# bldc-robot-main-board.net
KiCad netlist of a schematic drawn in Altium Designer
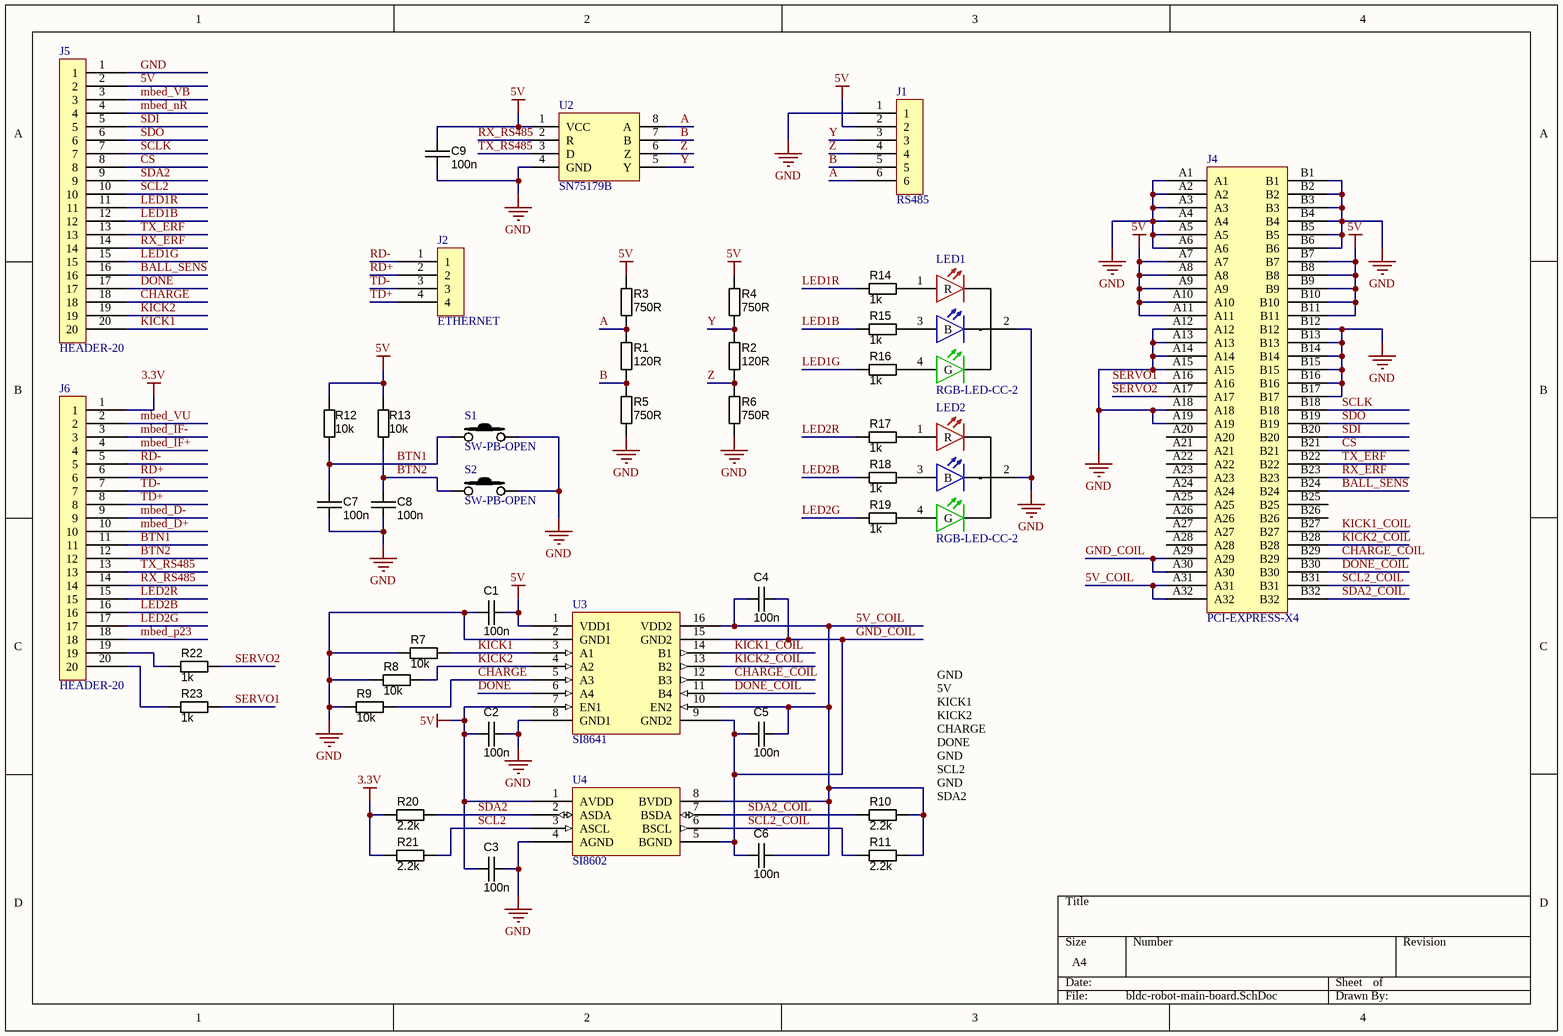
[diagram p0: bldc-robot-main-board.SchDoc]

(export (version "E")
  (design (tool "Eeschema 10.0.6"))
  (components
    (comp (ref "C1")
      (value "100n")
      (footprint "CAPC1608X90N")
      (description "Capacitor SMD Cer 100nF 10% 50V X7R 0603")
      (fields (field (name "TOLERANCE") "±10%"))
      (libsource (lib "PBL - Capacitors") (part "CAPC_100n_0603_X7R_50V_10%"))
    )
    (comp (ref "C2")
      (value "100n")
      (footprint "CAPC1608X90N")
      (description "Capacitor SMD Cer 100nF 10% 50V X7R 0603")
      (fields (field (name "TOLERANCE") "±10%"))
      (libsource (lib "PBL - Capacitors") (part "CAPC_100n_0603_X7R_50V_10%"))
    )
    (comp (ref "C3")
      (value "100n")
      (footprint "CAPC1608X90N")
      (description "Capacitor SMD Cer 100nF 10% 50V X7R 0603")
      (fields (field (name "TOLERANCE") "±10%"))
      (libsource (lib "PBL - Capacitors") (part "CAPC_100n_0603_X7R_50V_10%"))
    )
    (comp (ref "C4")
      (value "100n")
      (footprint "CAPC1608X90N")
      (description "Capacitor SMD Cer 100nF 10% 50V X7R 0603")
      (fields (field (name "TOLERANCE") "±10%"))
      (libsource (lib "PBL - Capacitors") (part "CAPC_100n_0603_X7R_50V_10%"))
    )
    (comp (ref "C5")
      (value "100n")
      (footprint "CAPC1608X90N")
      (description "Capacitor SMD Cer 100nF 10% 50V X7R 0603")
      (fields (field (name "TOLERANCE") "±10%"))
      (libsource (lib "PBL - Capacitors") (part "CAPC_100n_0603_X7R_50V_10%"))
    )
    (comp (ref "C6")
      (value "100n")
      (footprint "CAPC1608X90N")
      (description "Capacitor SMD Cer 100nF 10% 50V X7R 0603")
      (fields (field (name "TOLERANCE") "±10%"))
      (libsource (lib "PBL - Capacitors") (part "CAPC_100n_0603_X7R_50V_10%"))
    )
    (comp (ref "C7")
      (value "100n")
      (footprint "CAPC1608X90N")
      (description "Capacitor SMD Cer 100nF 10% 50V X7R 0603")
      (fields (field (name "TOLERANCE") "±10%"))
      (libsource (lib "PBL - Capacitors") (part "CAPC_100n_0603_X7R_50V_10%"))
    )
    (comp (ref "C8")
      (value "100n")
      (footprint "CAPC1608X90N")
      (description "Capacitor SMD Cer 100nF 10% 50V X7R 0603")
      (fields (field (name "TOLERANCE") "±10%"))
      (libsource (lib "PBL - Capacitors") (part "CAPC_100n_0603_X7R_50V_10%"))
    )
    (comp (ref "C9")
      (value "100n")
      (footprint "CAPC1608X90N")
      (description "Capacitor SMD Cer 100nF 10% 50V X7R 0603")
      (fields (field (name "TOLERANCE") "±10%"))
      (libsource (lib "PBL - Capacitors") (part "CAPC_100n_0603_X7R_50V_10%"))
    )
    (comp (ref "J1")
      (value "RS485")
      (footprint "MICRO-MATCH-6")
      (libsource (lib "connectors") (part "HEADER-6"))
    )
    (comp (ref "J2")
      (value "ETHERNET")
      (footprint "MICRO-MATCH-4")
      (libsource (lib "connectors") (part "HEADER-4"))
    )
    (comp (ref "J4")
      (value "PCI-EXPRESS-X4")
      (footprint "PCI-EXPRESS-X4-CARD-EDGE")
      (libsource (lib "connectors") (part "PCI-EXPRESS-X4"))
    )
    (comp (ref "J5")
      (value "HEADER-20")
      (footprint "MICRO-MATCH-20")
      (libsource (lib "connectors") (part "HEADER-20"))
    )
    (comp (ref "J6")
      (value "HEADER-20")
      (footprint "MICRO-MATCH-20")
      (libsource (lib "connectors") (part "HEADER-20"))
    )
    (comp (ref "LED1")
      (value "RGB-LED-CC-2")
      (footprint "RGB-LED-5mm")
      (libsource (lib "misc") (part "RGB-LED-CC-2"))
    )
    (comp (ref "LED2")
      (value "RGB-LED-CC-2")
      (footprint "RGB-LED-5mm")
      (libsource (lib "misc") (part "RGB-LED-CC-2"))
    )
    (comp (ref "R1")
      (value "120R")
      (footprint "RESC1608X55N")
      (description "Resistor SMD chip 120 Ohm 0.1W 5% 0603")
      (fields (field (name "TOLERANCE") "±5%"))
      (libsource (lib "") (part "RES_120R_0603_5%_2"))
    )
    (comp (ref "R2")
      (value "120R")
      (footprint "RESC1608X55N")
      (description "Resistor SMD chip 120 Ohm 0.1W 5% 0603")
      (fields (field (name "TOLERANCE") "±5%"))
      (libsource (lib "") (part "RES_120R_0603_5%_2"))
    )
    (comp (ref "R3")
      (value "750R")
      (footprint "RESC1608X55N")
      (description "Resistor SMD chip 120 Ohm 0.1W 5% 0603")
      (fields (field (name "TOLERANCE") "±5%"))
      (libsource (lib "") (part "RES_120R_0603_5%_2"))
    )
    (comp (ref "R4")
      (value "750R")
      (footprint "RESC1608X55N")
      (description "Resistor SMD chip 120 Ohm 0.1W 5% 0603")
      (fields (field (name "TOLERANCE") "±5%"))
      (libsource (lib "") (part "RES_120R_0603_5%_2"))
    )
    (comp (ref "R5")
      (value "750R")
      (footprint "RESC1608X55N")
      (description "Resistor SMD chip 120 Ohm 0.1W 5% 0603")
      (fields (field (name "TOLERANCE") "±5%"))
      (libsource (lib "") (part "RES_120R_0603_5%_2"))
    )
    (comp (ref "R6")
      (value "750R")
      (footprint "RESC1608X55N")
      (description "Resistor SMD chip 120 Ohm 0.1W 5% 0603")
      (fields (field (name "TOLERANCE") "±5%"))
      (libsource (lib "") (part "RES_120R_0603_5%_2"))
    )
    (comp (ref "R7")
      (value "10k")
      (footprint "RESC1608X55N")
      (description "Resistor SMD chip 120 Ohm 0.1W 5% 0603")
      (fields (field (name "TOLERANCE") "±5%"))
      (libsource (lib "") (part "RES_120R_0603_5%_1"))
    )
    (comp (ref "R8")
      (value "10k")
      (footprint "RESC1608X55N")
      (description "Resistor SMD chip 120 Ohm 0.1W 5% 0603")
      (fields (field (name "TOLERANCE") "±5%"))
      (libsource (lib "") (part "RES_120R_0603_5%_1"))
    )
    (comp (ref "R9")
      (value "10k")
      (footprint "RESC1608X55N")
      (description "Resistor SMD chip 120 Ohm 0.1W 5% 0603")
      (fields (field (name "TOLERANCE") "±5%"))
      (libsource (lib "") (part "RES_120R_0603_5%_1"))
    )
    (comp (ref "R10")
      (value "2.2k")
      (footprint "RESC1608X55N")
      (description "Resistor SMD chip 120 Ohm 0.1W 5% 0603")
      (fields (field (name "TOLERANCE") "±5%"))
      (libsource (lib "") (part "RES_120R_0603_5%_1"))
    )
    (comp (ref "R11")
      (value "2.2k")
      (footprint "RESC1608X55N")
      (description "Resistor SMD chip 120 Ohm 0.1W 5% 0603")
      (fields (field (name "TOLERANCE") "±5%"))
      (libsource (lib "") (part "RES_120R_0603_5%_1"))
    )
    (comp (ref "R12")
      (value "10k")
      (footprint "RESC1608X55N")
      (description "Resistor SMD chip 120 Ohm 0.1W 5% 0603")
      (fields (field (name "TOLERANCE") "±5%"))
      (libsource (lib "PBL - Resistors") (part "RES_120R_0603_5%"))
    )
    (comp (ref "R13")
      (value "10k")
      (footprint "RESC1608X55N")
      (description "Resistor SMD chip 120 Ohm 0.1W 5% 0603")
      (fields (field (name "TOLERANCE") "±5%"))
      (libsource (lib "PBL - Resistors") (part "RES_120R_0603_5%"))
    )
    (comp (ref "R14")
      (value "1k")
      (footprint "RESC1608X55N")
      (description "Resistor SMD chip 120 Ohm 0.1W 5% 0603")
      (fields (field (name "TOLERANCE") "±5%"))
      (libsource (lib "") (part "RES_120R_0603_5%_1"))
    )
    (comp (ref "R15")
      (value "1k")
      (footprint "RESC1608X55N")
      (description "Resistor SMD chip 120 Ohm 0.1W 5% 0603")
      (fields (field (name "TOLERANCE") "±5%"))
      (libsource (lib "") (part "RES_120R_0603_5%_1"))
    )
    (comp (ref "R16")
      (value "1k")
      (footprint "RESC1608X55N")
      (description "Resistor SMD chip 120 Ohm 0.1W 5% 0603")
      (fields (field (name "TOLERANCE") "±5%"))
      (libsource (lib "") (part "RES_120R_0603_5%_1"))
    )
    (comp (ref "R17")
      (value "1k")
      (footprint "RESC1608X55N")
      (description "Resistor SMD chip 120 Ohm 0.1W 5% 0603")
      (fields (field (name "TOLERANCE") "±5%"))
      (libsource (lib "") (part "RES_120R_0603_5%_1"))
    )
    (comp (ref "R18")
      (value "1k")
      (footprint "RESC1608X55N")
      (description "Resistor SMD chip 120 Ohm 0.1W 5% 0603")
      (fields (field (name "TOLERANCE") "±5%"))
      (libsource (lib "") (part "RES_120R_0603_5%_1"))
    )
    (comp (ref "R19")
      (value "1k")
      (footprint "RESC1608X55N")
      (description "Resistor SMD chip 120 Ohm 0.1W 5% 0603")
      (fields (field (name "TOLERANCE") "±5%"))
      (libsource (lib "") (part "RES_120R_0603_5%_1"))
    )
    (comp (ref "R20")
      (value "2.2k")
      (footprint "RESC1608X55N")
      (description "Resistor SMD chip 120 Ohm 0.1W 5% 0603")
      (fields (field (name "TOLERANCE") "±5%"))
      (libsource (lib "") (part "RES_120R_0603_5%_1"))
    )
    (comp (ref "R21")
      (value "2.2k")
      (footprint "RESC1608X55N")
      (description "Resistor SMD chip 120 Ohm 0.1W 5% 0603")
      (fields (field (name "TOLERANCE") "±5%"))
      (libsource (lib "") (part "RES_120R_0603_5%_1"))
    )
    (comp (ref "R22")
      (value "1k")
      (footprint "RESC1608X55N")
      (description "Resistor SMD chip 120 Ohm 0.1W 5% 0603")
      (fields (field (name "TOLERANCE") "±5%"))
      (libsource (lib "") (part "RES_120R_0603_5%_1"))
    )
    (comp (ref "R23")
      (value "1k")
      (footprint "RESC1608X55N")
      (description "Resistor SMD chip 120 Ohm 0.1W 5% 0603")
      (fields (field (name "TOLERANCE") "±5%"))
      (libsource (lib "") (part "RES_120R_0603_5%_1"))
    )
    (comp (ref "S1")
      (value "SW-PB-OPEN")
      (footprint "MC8US9R2A2M7RES")
      (libsource (lib "switches") (part "SW-PB-OPEN"))
    )
    (comp (ref "S2")
      (value "SW-PB-OPEN")
      (footprint "MC8US9R2A2M7RES")
      (libsource (lib "switches") (part "SW-PB-OPEN"))
    )
    (comp (ref "U2")
      (value "SN75179B")
      (footprint "SOIC-8")
      (libsource (lib "texas_instruments") (part "SN75179B"))
    )
    (comp (ref "U3") (value "SI8641") (footprint "SOIC16") (libsource (lib "digital") (part "SI8641")))
    (comp (ref "U4") (value "SI8602") (footprint "SOIC8") (libsource (lib "digital") (part "SI8602")))
  )
  (nets
    (net (code "1") (name "/5V_COIL") (class "Default")
      (node (ref "C4") (pin "2") (pintype "passive"))
      (node (ref "C5") (pin "1") (pintype "passive"))
      (node (ref "C6") (pin "1") (pintype "passive"))
      (node (ref "J4") (pin "A31") (pinfunction "A31_A31") (pintype "passive"))
      (node (ref "J4") (pin "A32") (pinfunction "A32_A32") (pintype "passive"))
      (node (ref "R10") (pin "2") (pinfunction "2_2") (pintype "passive"))
      (node (ref "R11") (pin "2") (pinfunction "2_2") (pintype "passive"))
      (node (ref "U3") (pin "10") (pinfunction "EN2_10") (pintype "input"))
      (node (ref "U3") (pin "16") (pinfunction "VDD2_16") (pintype "power_in"))
      (node (ref "U4") (pin "8") (pinfunction "BVDD_8") (pintype "power_in"))
    )
    (net (code "2") (name "/A") (class "Default")
      (node (ref "J1") (pin "6") (pinfunction "6_6") (pintype "passive"))
      (node (ref "R1") (pin "1") (pinfunction "1_1") (pintype "passive"))
      (node (ref "R3") (pin "2") (pinfunction "2_2") (pintype "passive"))
      (node (ref "U2") (pin "8") (pinfunction "A_8") (pintype "passive"))
    )
    (net (code "3") (name "/B") (class "Default")
      (node (ref "J1") (pin "5") (pinfunction "5_5") (pintype "passive"))
      (node (ref "R1") (pin "2") (pinfunction "2_2") (pintype "passive"))
      (node (ref "R5") (pin "1") (pinfunction "1_1") (pintype "passive"))
      (node (ref "U2") (pin "7") (pinfunction "B_7") (pintype "passive"))
    )
    (net (code "4") (name "/BALL_SENS") (class "Default")
      (node (ref "J4") (pin "B24") (pinfunction "B24_B24") (pintype "passive"))
      (node (ref "J5") (pin "16") (pinfunction "16_16") (pintype "passive"))
    )
    (net (code "5") (name "/BTN1") (class "Default")
      (node (ref "C7") (pin "1") (pintype "passive"))
      (node (ref "J6") (pin "11") (pinfunction "11_11") (pintype "passive"))
      (node (ref "R12") (pin "1") (pinfunction "1_1") (pintype "passive"))
      (node (ref "S1") (pin "1") (pinfunction "1_1") (pintype "passive"))
    )
    (net (code "6") (name "/BTN2") (class "Default")
      (node (ref "C8") (pin "1") (pintype "passive"))
      (node (ref "J6") (pin "12") (pinfunction "12_12") (pintype "passive"))
      (node (ref "R13") (pin "1") (pinfunction "1_1") (pintype "passive"))
      (node (ref "S2") (pin "1") (pinfunction "1_1") (pintype "passive"))
    )
    (net (code "7") (name "/CHARGE") (class "Default")
      (node (ref "J5") (pin "18") (pinfunction "18_18") (pintype "passive"))
      (node (ref "R9") (pin "2") (pinfunction "2_2") (pintype "passive"))
      (node (ref "U3") (pin "5") (pinfunction "A3_5") (pintype "input"))
    )
    (net (code "8") (name "/CHARGE_COIL") (class "Default")
      (node (ref "J4") (pin "B29") (pinfunction "B29_B29") (pintype "passive"))
      (node (ref "U3") (pin "12") (pinfunction "B3_12") (pintype "output"))
    )
    (net (code "9") (name "/CS") (class "Default")
      (node (ref "J4") (pin "B21") (pinfunction "B21_B21") (pintype "passive"))
      (node (ref "J5") (pin "8") (pinfunction "8_8") (pintype "passive"))
    )
    (net (code "10") (name "/DONE") (class "Default")
      (node (ref "J5") (pin "17") (pinfunction "17_17") (pintype "passive"))
      (node (ref "U3") (pin "6") (pinfunction "A4_6") (pintype "input"))
    )
    (net (code "11") (name "/DONE_COIL") (class "Default")
      (node (ref "J4") (pin "B30") (pinfunction "B30_B30") (pintype "passive"))
      (node (ref "U3") (pin "11") (pinfunction "B4_11") (pintype "input"))
    )
    (net (code "12") (name "/GND_COIL") (class "Default")
      (node (ref "C4") (pin "1") (pintype "passive"))
      (node (ref "C5") (pin "2") (pintype "passive"))
      (node (ref "C6") (pin "2") (pintype "passive"))
      (node (ref "J4") (pin "A29") (pinfunction "A29_A29") (pintype "passive"))
      (node (ref "J4") (pin "A30") (pinfunction "A30_A30") (pintype "passive"))
      (node (ref "U3") (pin "15") (pinfunction "GND2_15") (pintype "power_in"))
      (node (ref "U3") (pin "9") (pinfunction "GND2_9") (pintype "power_in"))
      (node (ref "U4") (pin "5") (pinfunction "BGND_5") (pintype "power_in"))
    )
    (net (code "13") (name "/KICK1") (class "Default")
      (node (ref "J5") (pin "20") (pinfunction "20_20") (pintype "passive"))
      (node (ref "R7") (pin "2") (pinfunction "2_2") (pintype "passive"))
      (node (ref "U3") (pin "3") (pinfunction "A1_3") (pintype "input"))
    )
    (net (code "14") (name "/KICK1_COIL") (class "Default")
      (node (ref "J4") (pin "B27") (pinfunction "B27_B27") (pintype "passive"))
      (node (ref "U3") (pin "14") (pinfunction "B1_14") (pintype "output"))
    )
    (net (code "15") (name "/KICK2") (class "Default")
      (node (ref "J5") (pin "19") (pinfunction "19_19") (pintype "passive"))
      (node (ref "R8") (pin "2") (pinfunction "2_2") (pintype "passive"))
      (node (ref "U3") (pin "4") (pinfunction "A2_4") (pintype "input"))
    )
    (net (code "16") (name "/KICK2_COIL") (class "Default")
      (node (ref "J4") (pin "B28") (pinfunction "B28_B28") (pintype "passive"))
      (node (ref "U3") (pin "13") (pinfunction "B2_13") (pintype "output"))
    )
    (net (code "17") (name "/LED1B") (class "Default")
      (node (ref "J5") (pin "12") (pinfunction "12_12") (pintype "passive"))
      (node (ref "R15") (pin "1") (pinfunction "1_1") (pintype "passive"))
    )
    (net (code "18") (name "/LED1G") (class "Default")
      (node (ref "J5") (pin "15") (pinfunction "15_15") (pintype "passive"))
      (node (ref "R16") (pin "1") (pinfunction "1_1") (pintype "passive"))
    )
    (net (code "19") (name "/LED1R") (class "Default")
      (node (ref "J5") (pin "11") (pinfunction "11_11") (pintype "passive"))
      (node (ref "R14") (pin "1") (pinfunction "1_1") (pintype "passive"))
    )
    (net (code "20") (name "/LED2B") (class "Default")
      (node (ref "J6") (pin "16") (pinfunction "16_16") (pintype "passive"))
      (node (ref "R18") (pin "1") (pinfunction "1_1") (pintype "passive"))
    )
    (net (code "21") (name "/LED2G") (class "Default")
      (node (ref "J6") (pin "17") (pinfunction "17_17") (pintype "passive"))
      (node (ref "R19") (pin "1") (pinfunction "1_1") (pintype "passive"))
    )
    (net (code "22") (name "/LED2R") (class "Default")
      (node (ref "J6") (pin "15") (pinfunction "15_15") (pintype "passive"))
      (node (ref "R17") (pin "1") (pinfunction "1_1") (pintype "passive"))
    )
    (net (code "23") (name "/RD+") (class "Default")
      (node (ref "J2") (pin "2") (pinfunction "2_2") (pintype "passive"))
      (node (ref "J6") (pin "6") (pinfunction "6_6") (pintype "passive"))
    )
    (net (code "24") (name "/RD-") (class "Default")
      (node (ref "J2") (pin "1") (pinfunction "1_1") (pintype "passive"))
      (node (ref "J6") (pin "5") (pinfunction "5_5") (pintype "passive"))
    )
    (net (code "25") (name "/RX_ERF") (class "Default")
      (node (ref "J4") (pin "B23") (pinfunction "B23_B23") (pintype "passive"))
      (node (ref "J5") (pin "14") (pinfunction "14_14") (pintype "passive"))
    )
    (net (code "26") (name "/RX_RS485") (class "Default")
      (node (ref "J6") (pin "14") (pinfunction "14_14") (pintype "passive"))
      (node (ref "U2") (pin "2") (pinfunction "R_2") (pintype "passive"))
    )
    (net (code "27") (name "/SCL2") (class "Default")
      (node (ref "J5") (pin "10") (pinfunction "10_10") (pintype "passive"))
      (node (ref "R21") (pin "2") (pinfunction "2_2") (pintype "passive"))
      (node (ref "U4") (pin "3") (pinfunction "ASCL_3") (pintype "input"))
    )
    (net (code "28") (name "/SCL2_COIL") (class "Default")
      (node (ref "J4") (pin "B31") (pinfunction "B31_B31") (pintype "passive"))
      (node (ref "R11") (pin "1") (pinfunction "1_1") (pintype "passive"))
      (node (ref "U4") (pin "6") (pinfunction "BSCL_6") (pintype "output"))
    )
    (net (code "29") (name "/SCLK") (class "Default")
      (node (ref "J4") (pin "B18") (pinfunction "B18_B18") (pintype "passive"))
      (node (ref "J5") (pin "7") (pinfunction "7_7") (pintype "passive"))
    )
    (net (code "30") (name "/SDA2") (class "Default")
      (node (ref "J5") (pin "9") (pinfunction "9_9") (pintype "passive"))
      (node (ref "R20") (pin "2") (pinfunction "2_2") (pintype "passive"))
      (node (ref "U4") (pin "2") (pinfunction "ASDA_2") (pintype "bidirectional"))
    )
    (net (code "31") (name "/SDA2_COIL") (class "Default")
      (node (ref "J4") (pin "B32") (pinfunction "B32_B32") (pintype "passive"))
      (node (ref "R10") (pin "1") (pinfunction "1_1") (pintype "passive"))
      (node (ref "U4") (pin "7") (pinfunction "BSDA_7") (pintype "bidirectional"))
    )
    (net (code "32") (name "/SDI") (class "Default")
      (node (ref "J4") (pin "B20") (pinfunction "B20_B20") (pintype "passive"))
      (node (ref "J5") (pin "5") (pinfunction "5_5") (pintype "passive"))
    )
    (net (code "33") (name "/SDO") (class "Default")
      (node (ref "J4") (pin "B19") (pinfunction "B19_B19") (pintype "passive"))
      (node (ref "J5") (pin "6") (pinfunction "6_6") (pintype "passive"))
    )
    (net (code "34") (name "/SERVO1") (class "Default")
      (node (ref "J4") (pin "A16") (pinfunction "A16_A16") (pintype "passive"))
      (node (ref "R23") (pin "2") (pinfunction "2_2") (pintype "passive"))
    )
    (net (code "35") (name "/SERVO2") (class "Default")
      (node (ref "J4") (pin "A17") (pinfunction "A17_A17") (pintype "passive"))
      (node (ref "R22") (pin "2") (pinfunction "2_2") (pintype "passive"))
    )
    (net (code "36") (name "/TD+") (class "Default")
      (node (ref "J2") (pin "4") (pinfunction "4_4") (pintype "passive"))
      (node (ref "J6") (pin "8") (pinfunction "8_8") (pintype "passive"))
    )
    (net (code "37") (name "/TD-") (class "Default")
      (node (ref "J2") (pin "3") (pinfunction "3_3") (pintype "passive"))
      (node (ref "J6") (pin "7") (pinfunction "7_7") (pintype "passive"))
    )
    (net (code "38") (name "/TX_ERF") (class "Default")
      (node (ref "J4") (pin "B22") (pinfunction "B22_B22") (pintype "passive"))
      (node (ref "J5") (pin "13") (pinfunction "13_13") (pintype "passive"))
    )
    (net (code "39") (name "/TX_RS485") (class "Default")
      (node (ref "J6") (pin "13") (pinfunction "13_13") (pintype "passive"))
      (node (ref "U2") (pin "3") (pinfunction "D_3") (pintype "passive"))
    )
    (net (code "40") (name "/Y") (class "Default")
      (node (ref "J1") (pin "3") (pinfunction "3_3") (pintype "passive"))
      (node (ref "R2") (pin "1") (pinfunction "1_1") (pintype "passive"))
      (node (ref "R4") (pin "2") (pinfunction "2_2") (pintype "passive"))
      (node (ref "U2") (pin "5") (pinfunction "Y_5") (pintype "passive"))
    )
    (net (code "41") (name "/Z") (class "Default")
      (node (ref "J1") (pin "4") (pinfunction "4_4") (pintype "passive"))
      (node (ref "R2") (pin "2") (pinfunction "2_2") (pintype "passive"))
      (node (ref "R6") (pin "1") (pinfunction "1_1") (pintype "passive"))
      (node (ref "U2") (pin "6") (pinfunction "Z_6") (pintype "passive"))
    )
    (net (code "42") (name "/mbed_D+") (class "Default")
      (node (ref "J6") (pin "10") (pinfunction "10_10") (pintype "passive"))
    )
    (net (code "43") (name "/mbed_D-") (class "Default")
      (node (ref "J6") (pin "9") (pinfunction "9_9") (pintype "passive"))
    )
    (net (code "44") (name "/mbed_IF+") (class "Default")
      (node (ref "J6") (pin "4") (pinfunction "4_4") (pintype "passive"))
    )
    (net (code "45") (name "/mbed_IF-") (class "Default")
      (node (ref "J6") (pin "3") (pinfunction "3_3") (pintype "passive"))
    )
    (net (code "46") (name "/mbed_VB") (class "Default")
      (node (ref "J5") (pin "3") (pinfunction "3_3") (pintype "passive"))
    )
    (net (code "47") (name "/mbed_VU") (class "Default")
      (node (ref "J6") (pin "2") (pinfunction "2_2") (pintype "passive"))
    )
    (net (code "48") (name "/mbed_nR") (class "Default")
      (node (ref "J5") (pin "4") (pinfunction "4_4") (pintype "passive"))
    )
    (net (code "49") (name "/mbed_p23") (class "Default")
      (node (ref "J6") (pin "18") (pinfunction "18_18") (pintype "passive"))
    )
    (net (code "50") (name "3.3V") (class "Default")
      (node (ref "J6") (pin "1") (pinfunction "1_1") (pintype "passive"))
      (node (ref "R20") (pin "1") (pinfunction "1_1") (pintype "passive"))
      (node (ref "R21") (pin "1") (pinfunction "1_1") (pintype "passive"))
    )
    (net (code "51") (name "5V") (class "Default")
      (node (ref "C1") (pin "1") (pintype "passive"))
      (node (ref "C2") (pin "2") (pintype "passive"))
      (node (ref "C3") (pin "2") (pintype "passive"))
      (node (ref "C9") (pin "1") (pintype "passive"))
      (node (ref "J1") (pin "2") (pinfunction "2_2") (pintype "passive"))
      (node (ref "J4") (pin "A10") (pinfunction "A10_A10") (pintype "passive"))
      (node (ref "J4") (pin "A11") (pinfunction "A11_A11") (pintype "passive"))
      (node (ref "J4") (pin "A7") (pinfunction "A7_A7") (pintype "passive"))
      (node (ref "J4") (pin "A8") (pinfunction "A8_A8") (pintype "passive"))
      (node (ref "J4") (pin "A9") (pinfunction "A9_A9") (pintype "passive"))
      (node (ref "J4") (pin "B10") (pinfunction "B10_B10") (pintype "passive"))
      (node (ref "J4") (pin "B11") (pinfunction "B11_B11") (pintype "passive"))
      (node (ref "J4") (pin "B7") (pinfunction "B7_B7") (pintype "passive"))
      (node (ref "J4") (pin "B8") (pinfunction "B8_B8") (pintype "passive"))
      (node (ref "J4") (pin "B9") (pinfunction "B9_B9") (pintype "passive"))
      (node (ref "J5") (pin "2") (pinfunction "2_2") (pintype "passive"))
      (node (ref "R12") (pin "2") (pinfunction "2_2") (pintype "passive"))
      (node (ref "R13") (pin "2") (pinfunction "2_2") (pintype "passive"))
      (node (ref "R3") (pin "1") (pinfunction "1_1") (pintype "passive"))
      (node (ref "R4") (pin "1") (pinfunction "1_1") (pintype "passive"))
      (node (ref "U2") (pin "1") (pinfunction "VCC_1") (pintype "passive"))
      (node (ref "U3") (pin "1") (pinfunction "VDD1_1") (pintype "power_in"))
      (node (ref "U3") (pin "7") (pinfunction "EN1_7") (pintype "input"))
      (node (ref "U4") (pin "1") (pinfunction "AVDD_1") (pintype "power_in"))
    )
    (net (code "52") (name "GND") (class "Default")
      (node (ref "C1") (pin "2") (pintype "passive"))
      (node (ref "C2") (pin "1") (pintype "passive"))
      (node (ref "C3") (pin "1") (pintype "passive"))
      (node (ref "C7") (pin "2") (pintype "passive"))
      (node (ref "C8") (pin "2") (pintype "passive"))
      (node (ref "C9") (pin "2") (pintype "passive"))
      (node (ref "J1") (pin "1") (pinfunction "1_1") (pintype "passive"))
      (node (ref "J4") (pin "A1") (pinfunction "A1_A1") (pintype "passive"))
      (node (ref "J4") (pin "A12") (pinfunction "A12_A12") (pintype "passive"))
      (node (ref "J4") (pin "A13") (pinfunction "A13_A13") (pintype "passive"))
      (node (ref "J4") (pin "A14") (pinfunction "A14_A14") (pintype "passive"))
      (node (ref "J4") (pin "A15") (pinfunction "A15_A15") (pintype "passive"))
      (node (ref "J4") (pin "A18") (pinfunction "A18_A18") (pintype "passive"))
      (node (ref "J4") (pin "A19") (pinfunction "A19_A19") (pintype "passive"))
      (node (ref "J4") (pin "A2") (pinfunction "A2_A2") (pintype "passive"))
      (node (ref "J4") (pin "A3") (pinfunction "A3_A3") (pintype "passive"))
      (node (ref "J4") (pin "A4") (pinfunction "A4_A4") (pintype "passive"))
      (node (ref "J4") (pin "A5") (pinfunction "A5_A5") (pintype "passive"))
      (node (ref "J4") (pin "A6") (pinfunction "A6_A6") (pintype "passive"))
      (node (ref "J4") (pin "B1") (pinfunction "B1_B1") (pintype "passive"))
      (node (ref "J4") (pin "B12") (pinfunction "B12_B12") (pintype "passive"))
      (node (ref "J4") (pin "B13") (pinfunction "B13_B13") (pintype "passive"))
      (node (ref "J4") (pin "B14") (pinfunction "B14_B14") (pintype "passive"))
      (node (ref "J4") (pin "B15") (pinfunction "B15_B15") (pintype "passive"))
      (node (ref "J4") (pin "B16") (pinfunction "B16_B16") (pintype "passive"))
      (node (ref "J4") (pin "B17") (pinfunction "B17_B17") (pintype "passive"))
      (node (ref "J4") (pin "B2") (pinfunction "B2_B2") (pintype "passive"))
      (node (ref "J4") (pin "B3") (pinfunction "B3_B3") (pintype "passive"))
      (node (ref "J4") (pin "B4") (pinfunction "B4_B4") (pintype "passive"))
      (node (ref "J4") (pin "B5") (pinfunction "B5_B5") (pintype "passive"))
      (node (ref "J4") (pin "B6") (pinfunction "B6_B6") (pintype "passive"))
      (node (ref "J5") (pin "1") (pinfunction "1_1") (pintype "passive"))
      (node (ref "LED1") (pin "2") (pinfunction "-_2") (pintype "passive"))
      (node (ref "LED2") (pin "2") (pinfunction "-_2") (pintype "passive"))
      (node (ref "R5") (pin "2") (pinfunction "2_2") (pintype "passive"))
      (node (ref "R6") (pin "2") (pinfunction "2_2") (pintype "passive"))
      (node (ref "R7") (pin "1") (pinfunction "1_1") (pintype "passive"))
      (node (ref "R8") (pin "1") (pinfunction "1_1") (pintype "passive"))
      (node (ref "R9") (pin "1") (pinfunction "1_1") (pintype "passive"))
      (node (ref "S1") (pin "2") (pinfunction "2_2") (pintype "passive"))
      (node (ref "S2") (pin "2") (pinfunction "2_2") (pintype "passive"))
      (node (ref "U2") (pin "4") (pinfunction "GND_4") (pintype "passive"))
      (node (ref "U3") (pin "2") (pinfunction "GND1_2") (pintype "power_in"))
      (node (ref "U3") (pin "8") (pinfunction "GND1_8") (pintype "power_in"))
      (node (ref "U4") (pin "4") (pinfunction "AGND_4") (pintype "power_in"))
    )
    (net (code "53") (name "Net-(J6-Pad19)") (class "Default")
      (node (ref "J6") (pin "19") (pinfunction "19_19") (pintype "passive"))
      (node (ref "R22") (pin "1") (pinfunction "1_1") (pintype "passive"))
    )
    (net (code "54") (name "Net-(J6-Pad20)") (class "Default")
      (node (ref "J6") (pin "20") (pinfunction "20_20") (pintype "passive"))
      (node (ref "R23") (pin "1") (pinfunction "1_1") (pintype "passive"))
    )
    (net (code "55") (name "Net-(LED1-B)") (class "Default")
      (node (ref "LED1") (pin "3") (pinfunction "B_3") (pintype "passive"))
      (node (ref "R15") (pin "2") (pinfunction "2_2") (pintype "passive"))
    )
    (net (code "56") (name "Net-(LED1-G)") (class "Default")
      (node (ref "LED1") (pin "4") (pinfunction "G_4") (pintype "passive"))
      (node (ref "R16") (pin "2") (pinfunction "2_2") (pintype "passive"))
    )
    (net (code "57") (name "Net-(LED1-R)") (class "Default")
      (node (ref "LED1") (pin "1") (pinfunction "R_1") (pintype "passive"))
      (node (ref "R14") (pin "2") (pinfunction "2_2") (pintype "passive"))
    )
    (net (code "58") (name "Net-(LED2-B)") (class "Default")
      (node (ref "LED2") (pin "3") (pinfunction "B_3") (pintype "passive"))
      (node (ref "R18") (pin "2") (pinfunction "2_2") (pintype "passive"))
    )
    (net (code "59") (name "Net-(LED2-G)") (class "Default")
      (node (ref "LED2") (pin "4") (pinfunction "G_4") (pintype "passive"))
      (node (ref "R19") (pin "2") (pinfunction "2_2") (pintype "passive"))
    )
    (net (code "60") (name "Net-(LED2-R)") (class "Default")
      (node (ref "LED2") (pin "1") (pinfunction "R_1") (pintype "passive"))
      (node (ref "R17") (pin "2") (pinfunction "2_2") (pintype "passive"))
    )
    (net (code "61") (name "unconnected-(J4-PadA20)") (class "Default")
      (node (ref "J4") (pin "A20") (pinfunction "A20_A20") (pintype "passive"))
    )
    (net (code "62") (name "unconnected-(J4-PadA21)") (class "Default")
      (node (ref "J4") (pin "A21") (pinfunction "A21_A21") (pintype "passive"))
    )
    (net (code "63") (name "unconnected-(J4-PadA22)") (class "Default")
      (node (ref "J4") (pin "A22") (pinfunction "A22_A22") (pintype "passive"))
    )
    (net (code "64") (name "unconnected-(J4-PadA23)") (class "Default")
      (node (ref "J4") (pin "A23") (pinfunction "A23_A23") (pintype "passive"))
    )
    (net (code "65") (name "unconnected-(J4-PadA24)") (class "Default")
      (node (ref "J4") (pin "A24") (pinfunction "A24_A24") (pintype "passive"))
    )
    (net (code "66") (name "unconnected-(J4-PadA25)") (class "Default")
      (node (ref "J4") (pin "A25") (pinfunction "A25_A25") (pintype "passive"))
    )
    (net (code "67") (name "unconnected-(J4-PadA26)") (class "Default")
      (node (ref "J4") (pin "A26") (pinfunction "A26_A26") (pintype "passive"))
    )
    (net (code "68") (name "unconnected-(J4-PadA27)") (class "Default")
      (node (ref "J4") (pin "A27") (pinfunction "A27_A27") (pintype "passive"))
    )
    (net (code "69") (name "unconnected-(J4-PadA28)") (class "Default")
      (node (ref "J4") (pin "A28") (pinfunction "A28_A28") (pintype "passive"))
    )
    (net (code "70") (name "unconnected-(J4-PadB25)") (class "Default")
      (node (ref "J4") (pin "B25") (pinfunction "B25_B25") (pintype "passive"))
    )
    (net (code "71") (name "unconnected-(J4-PadB26)") (class "Default")
      (node (ref "J4") (pin "B26") (pinfunction "B26_B26") (pintype "passive"))
    )
  )
)
